# untitled.net
KiCad netlist of a schematic drawn in EAGLE
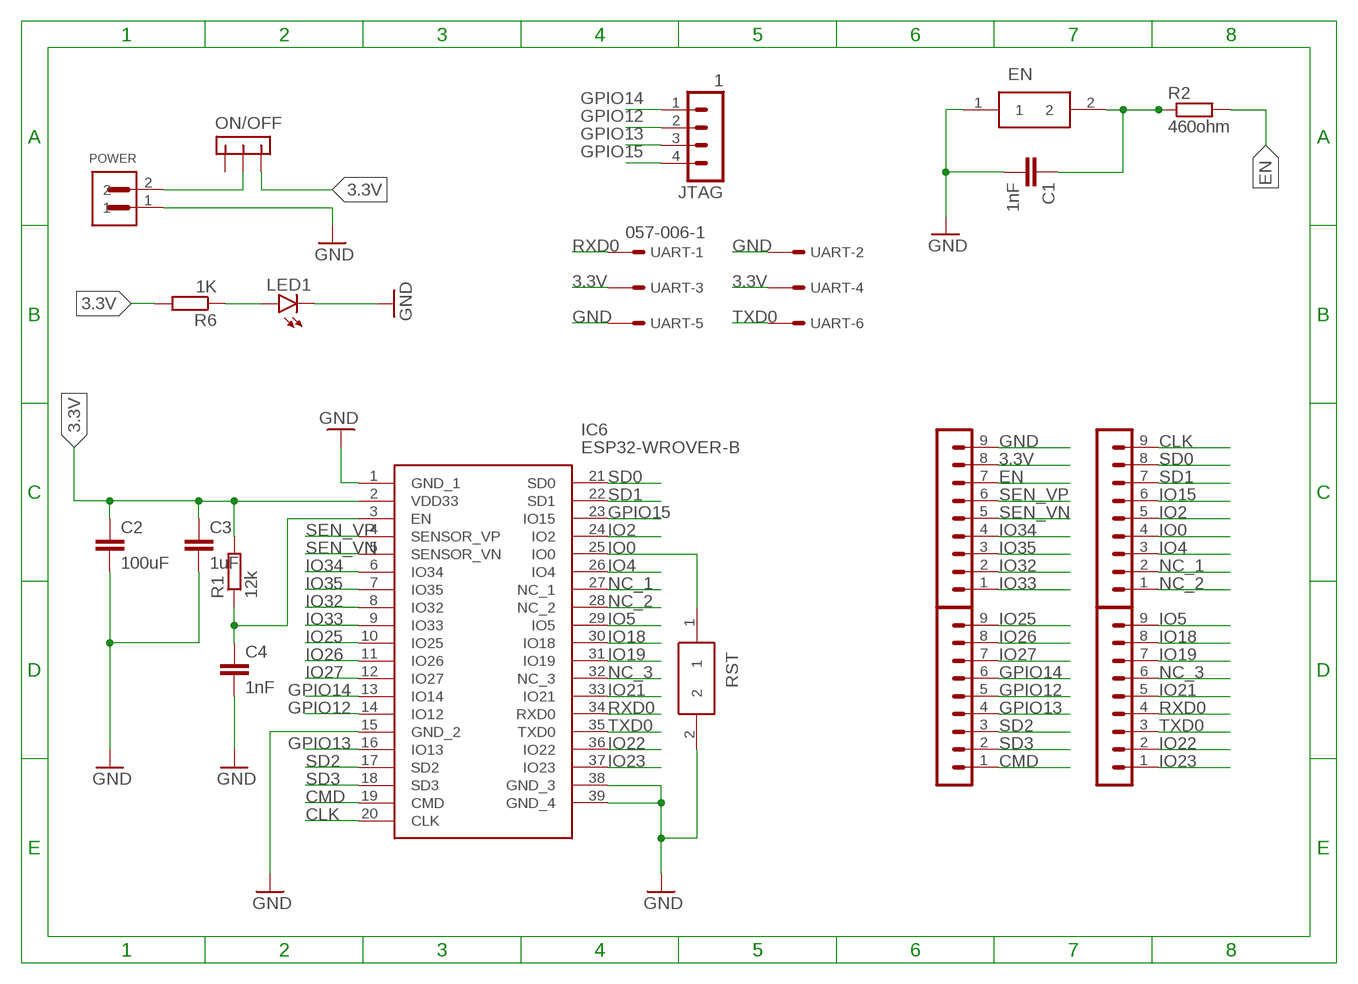
[diagram p0: schematic, sheet 1]

(export (version "E")
  (design (tool "Eeschema 10.0.6"))
  (components
    (comp (ref "C1")
      (value "1nF")
      (footprint "eagle-import:C0805")
      (libsource (lib "eagle-import") (part "C-EU_805C0805"))
    )
    (comp (ref "C2")
      (value "100uF")
      (footprint "eagle-import:C1206")
      (libsource (lib "eagle-import") (part "C-EU_1206C1206"))
    )
    (comp (ref "C3")
      (value "1uF")
      (footprint "eagle-import:C0805")
      (libsource (lib "eagle-import") (part "C-EU_805C0805"))
    )
    (comp (ref "C4")
      (value "1nF")
      (footprint "eagle-import:C0805")
      (libsource (lib "eagle-import") (part "C-EU_805C0805"))
    )
    (comp (ref "EN")
      (value "FSMSMTR")
      (footprint "eagle-import:FSMSM")
      (fields (field (name "MOUSER_PART_NUMBER") "506-FSMSMTR") (field (name "RS_PART_NUMBER") "1680547"))
      (libsource (lib "eagle-import") (part "FSMSMTR"))
    )
    (comp (ref "IC6")
      (value "ESP32-WROVER-B")
      (footprint "eagle-import:ESP32WROVERIB16MB")
      (fields (field (name "MOUSER_PART_NUMBER") "356-ESP32-WROVER-B"))
      (libsource (lib "eagle-import") (part "ESP32-WROVER-B"))
    )
    (comp (ref "JTAG")
      (value "1")
      (footprint "eagle-import:MA04-1")
      (libsource (lib "eagle-import") (part "MA04-1"))
    )
    (comp (ref "LED1")
      (value "LEDSMT1206")
      (footprint "eagle-import:1206")
      (libsource (lib "eagle-import") (part "LEDSMT1206"))
    )
    (comp (ref "ON/OFF")
      (value "-CON3")
      (footprint "eagle-import:CON3")
      (libsource (lib "eagle-import") (part "-CON3"))
    )
    (comp (ref "POWER")
      (value "S2B-PH-SM4-TB")
      (footprint "eagle-import:JST_S2B-PH-SM4-TB")
      (fields (field (name "MF") "JST Sales"))
      (libsource (lib "eagle-import") (part "S2B-PH-SM4-TB"))
    )
    (comp (ref "R1")
      (value "12k")
      (footprint "eagle-import:R0805")
      (libsource (lib "eagle-import") (part "R-EU_805R0805"))
    )
    (comp (ref "R2")
      (value "460ohm")
      (footprint "eagle-import:R0805")
      (libsource (lib "eagle-import") (part "R-EU_805R0805"))
    )
    (comp (ref "R6")
      (value "1K")
      (footprint "eagle-import:R1206")
      (libsource (lib "eagle-import") (part "R-EU_R1206"))
    )
    (comp (ref "RST")
      (value "FSMSMTR")
      (footprint "eagle-import:FSMSM")
      (fields (field (name "MOUSER_PART_NUMBER") "506-FSMSMTR") (field (name "RS_PART_NUMBER") "1680547"))
      (libsource (lib "eagle-import") (part "FSMSMTR"))
    )
    (comp (ref "SV1")
      (value "PINHEADER-1X9")
      (footprint "eagle-import:MA09-1")
      (libsource (lib "eagle-import") (part "PINHEADER-1X9"))
    )
    (comp (ref "SV2")
      (value "PINHEADER-1X9")
      (footprint "eagle-import:MA09-1")
      (libsource (lib "eagle-import") (part "PINHEADER-1X9"))
    )
    (comp (ref "SV5")
      (value "PINHEADER-1X9")
      (footprint "eagle-import:MA09-1")
      (libsource (lib "eagle-import") (part "PINHEADER-1X9"))
    )
    (comp (ref "SV6")
      (value "PINHEADER-1X9")
      (footprint "eagle-import:MA09-1")
      (libsource (lib "eagle-import") (part "PINHEADER-1X9"))
    )
    (comp (ref "UART")
      (value "057-006-1")
      (footprint "eagle-import:057-006-1")
      (libsource (lib "eagle-import") (part "057-006-1"))
    )
  )
  (nets
    (net (code "1") (name "3.3V") (class "Default")
      (node (ref "C2") (pin "1") (pinfunction "1_1") (pintype "passive"))
      (node (ref "C3") (pin "1") (pinfunction "1_1") (pintype "passive"))
      (node (ref "IC6") (pin "2") (pinfunction "VDD33_2") (pintype "bidirectional"))
      (node (ref "ON/OFF") (pin "P$1") (pinfunction "1_P$1") (pintype "passive"))
      (node (ref "R1") (pin "2") (pinfunction "2_2") (pintype "passive"))
      (node (ref "R6") (pin "2") (pinfunction "2_2") (pintype "passive"))
      (node (ref "SV5") (pin "8") (pinfunction "8_8") (pintype "passive"))
      (node (ref "UART") (pin "3") (pinfunction "S_3") (pintype "passive"))
      (node (ref "UART") (pin "4") (pinfunction "S_4") (pintype "passive"))
    )
    (net (code "2") (name "CLK") (class "Default")
      (node (ref "IC6") (pin "20") (pinfunction "CLK_20") (pintype "bidirectional"))
      (node (ref "SV1") (pin "9") (pinfunction "9_9") (pintype "passive"))
    )
    (net (code "3") (name "CMD") (class "Default")
      (node (ref "IC6") (pin "19") (pinfunction "CMD_19") (pintype "bidirectional"))
      (node (ref "SV6") (pin "1") (pinfunction "1_1") (pintype "passive"))
    )
    (net (code "4") (name "EN") (class "Default")
      (node (ref "C1") (pin "1") (pinfunction "1_1") (pintype "passive"))
      (node (ref "C4") (pin "1") (pinfunction "1_1") (pintype "passive"))
      (node (ref "EN") (pin "2") (pinfunction "2_2") (pintype "bidirectional"))
      (node (ref "IC6") (pin "3") (pinfunction "EN_3") (pintype "bidirectional"))
      (node (ref "R1") (pin "1") (pinfunction "1_1") (pintype "passive"))
      (node (ref "R2") (pin "1") (pinfunction "1_1") (pintype "passive"))
      (node (ref "R2") (pin "2") (pinfunction "2_2") (pintype "passive"))
      (node (ref "SV5") (pin "7") (pinfunction "7_7") (pintype "passive"))
    )
    (net (code "5") (name "GND") (class "Default")
      (node (ref "C1") (pin "2") (pinfunction "2_2") (pintype "passive"))
      (node (ref "C2") (pin "2") (pinfunction "2_2") (pintype "passive"))
      (node (ref "C3") (pin "2") (pinfunction "2_2") (pintype "passive"))
      (node (ref "C4") (pin "2") (pinfunction "2_2") (pintype "passive"))
      (node (ref "EN") (pin "1") (pinfunction "1_1") (pintype "bidirectional"))
      (node (ref "IC6") (pin "1") (pinfunction "GND_1_1") (pintype "bidirectional"))
      (node (ref "IC6") (pin "15") (pinfunction "GND_2_15") (pintype "bidirectional"))
      (node (ref "IC6") (pin "38") (pinfunction "GND_3_38") (pintype "bidirectional"))
      (node (ref "IC6") (pin "39") (pinfunction "GND_4_39") (pintype "bidirectional"))
      (node (ref "LED1") (pin "C") (pinfunction "C_C") (pintype "passive"))
      (node (ref "POWER") (pin "1") (pinfunction "1_1") (pintype "passive"))
      (node (ref "RST") (pin "2") (pinfunction "2_2") (pintype "bidirectional"))
      (node (ref "SV5") (pin "9") (pinfunction "9_9") (pintype "passive"))
      (node (ref "UART") (pin "2") (pinfunction "S_2") (pintype "passive"))
      (node (ref "UART") (pin "5") (pinfunction "S_5") (pintype "passive"))
    )
    (net (code "6") (name "GPIO12") (class "Default")
      (node (ref "IC6") (pin "14") (pinfunction "IO12_14") (pintype "bidirectional"))
      (node (ref "JTAG") (pin "2") (pinfunction "2_2") (pintype "passive"))
      (node (ref "SV6") (pin "5") (pinfunction "5_5") (pintype "passive"))
    )
    (net (code "7") (name "GPIO13") (class "Default")
      (node (ref "IC6") (pin "16") (pinfunction "IO13_16") (pintype "bidirectional"))
      (node (ref "JTAG") (pin "3") (pinfunction "3_3") (pintype "passive"))
      (node (ref "SV6") (pin "4") (pinfunction "4_4") (pintype "passive"))
    )
    (net (code "8") (name "GPIO14") (class "Default")
      (node (ref "IC6") (pin "13") (pinfunction "IO14_13") (pintype "bidirectional"))
      (node (ref "JTAG") (pin "1") (pinfunction "1_1") (pintype "passive"))
      (node (ref "SV6") (pin "6") (pinfunction "6_6") (pintype "passive"))
    )
    (net (code "9") (name "GPIO15") (class "Default")
      (node (ref "IC6") (pin "23") (pinfunction "IO15_23") (pintype "bidirectional"))
      (node (ref "JTAG") (pin "4") (pinfunction "4_4") (pintype "passive"))
    )
    (net (code "10") (name "IO0") (class "Default")
      (node (ref "IC6") (pin "25") (pinfunction "IO0_25") (pintype "bidirectional"))
      (node (ref "RST") (pin "1") (pinfunction "1_1") (pintype "bidirectional"))
      (node (ref "SV1") (pin "4") (pinfunction "4_4") (pintype "passive"))
    )
    (net (code "11") (name "IO2") (class "Default")
      (node (ref "IC6") (pin "24") (pinfunction "IO2_24") (pintype "bidirectional"))
      (node (ref "SV1") (pin "5") (pinfunction "5_5") (pintype "passive"))
    )
    (net (code "12") (name "IO4") (class "Default")
      (node (ref "IC6") (pin "26") (pinfunction "IO4_26") (pintype "bidirectional"))
      (node (ref "SV1") (pin "3") (pinfunction "3_3") (pintype "passive"))
    )
    (net (code "13") (name "IO5") (class "Default")
      (node (ref "IC6") (pin "29") (pinfunction "IO5_29") (pintype "bidirectional"))
      (node (ref "SV2") (pin "9") (pinfunction "9_9") (pintype "passive"))
    )
    (net (code "14") (name "IO15") (class "Default")
      (node (ref "SV1") (pin "6") (pinfunction "6_6") (pintype "passive"))
    )
    (net (code "15") (name "IO18") (class "Default")
      (node (ref "IC6") (pin "30") (pinfunction "IO18_30") (pintype "bidirectional"))
      (node (ref "SV2") (pin "8") (pinfunction "8_8") (pintype "passive"))
    )
    (net (code "16") (name "IO19") (class "Default")
      (node (ref "IC6") (pin "31") (pinfunction "IO19_31") (pintype "bidirectional"))
      (node (ref "SV2") (pin "7") (pinfunction "7_7") (pintype "passive"))
    )
    (net (code "17") (name "IO21") (class "Default")
      (node (ref "IC6") (pin "33") (pinfunction "IO21_33") (pintype "bidirectional"))
      (node (ref "SV2") (pin "5") (pinfunction "5_5") (pintype "passive"))
    )
    (net (code "18") (name "IO22") (class "Default")
      (node (ref "IC6") (pin "36") (pinfunction "IO22_36") (pintype "bidirectional"))
      (node (ref "SV2") (pin "2") (pinfunction "2_2") (pintype "passive"))
    )
    (net (code "19") (name "IO23") (class "Default")
      (node (ref "IC6") (pin "37") (pinfunction "IO23_37") (pintype "bidirectional"))
      (node (ref "SV2") (pin "1") (pinfunction "1_1") (pintype "passive"))
    )
    (net (code "20") (name "IO25") (class "Default")
      (node (ref "IC6") (pin "10") (pinfunction "IO25_10") (pintype "bidirectional"))
      (node (ref "SV6") (pin "9") (pinfunction "9_9") (pintype "passive"))
    )
    (net (code "21") (name "IO26") (class "Default")
      (node (ref "IC6") (pin "11") (pinfunction "IO26_11") (pintype "bidirectional"))
      (node (ref "SV6") (pin "8") (pinfunction "8_8") (pintype "passive"))
    )
    (net (code "22") (name "IO27") (class "Default")
      (node (ref "IC6") (pin "12") (pinfunction "IO27_12") (pintype "bidirectional"))
      (node (ref "SV6") (pin "7") (pinfunction "7_7") (pintype "passive"))
    )
    (net (code "23") (name "IO32") (class "Default")
      (node (ref "IC6") (pin "8") (pinfunction "IO32_8") (pintype "bidirectional"))
      (node (ref "SV5") (pin "2") (pinfunction "2_2") (pintype "passive"))
    )
    (net (code "24") (name "IO33") (class "Default")
      (node (ref "IC6") (pin "9") (pinfunction "IO33_9") (pintype "bidirectional"))
      (node (ref "SV5") (pin "1") (pinfunction "1_1") (pintype "passive"))
    )
    (net (code "25") (name "IO34") (class "Default")
      (node (ref "IC6") (pin "6") (pinfunction "IO34_6") (pintype "bidirectional"))
      (node (ref "SV5") (pin "4") (pinfunction "4_4") (pintype "passive"))
    )
    (net (code "26") (name "IO35") (class "Default")
      (node (ref "IC6") (pin "7") (pinfunction "IO35_7") (pintype "bidirectional"))
      (node (ref "SV5") (pin "3") (pinfunction "3_3") (pintype "passive"))
    )
    (net (code "27") (name "NC_1") (class "Default")
      (node (ref "IC6") (pin "27") (pinfunction "NC_1_27") (pintype "bidirectional"))
      (node (ref "SV1") (pin "2") (pinfunction "2_2") (pintype "passive"))
    )
    (net (code "28") (name "NC_2") (class "Default")
      (node (ref "IC6") (pin "28") (pinfunction "NC_2_28") (pintype "bidirectional"))
      (node (ref "SV1") (pin "1") (pinfunction "1_1") (pintype "passive"))
    )
    (net (code "29") (name "NC_3") (class "Default")
      (node (ref "IC6") (pin "32") (pinfunction "NC_3_32") (pintype "bidirectional"))
      (node (ref "SV2") (pin "6") (pinfunction "6_6") (pintype "passive"))
    )
    (net (code "30") (name "Net-(LED1-PadA)") (class "Default")
      (node (ref "LED1") (pin "A") (pinfunction "A_A") (pintype "passive"))
      (node (ref "R6") (pin "1") (pinfunction "1_1") (pintype "passive"))
    )
    (net (code "31") (name "Net-(ON/OFF-2)") (class "Default")
      (node (ref "ON/OFF") (pin "P$2") (pinfunction "2_P$2") (pintype "passive"))
      (node (ref "POWER") (pin "2") (pinfunction "2_2") (pintype "passive"))
    )
    (net (code "32") (name "RXD0") (class "Default")
      (node (ref "IC6") (pin "34") (pinfunction "RXD0_34") (pintype "bidirectional"))
      (node (ref "SV2") (pin "4") (pinfunction "4_4") (pintype "passive"))
      (node (ref "UART") (pin "1") (pinfunction "S_1") (pintype "passive"))
    )
    (net (code "33") (name "SD0") (class "Default")
      (node (ref "IC6") (pin "21") (pinfunction "SD0_21") (pintype "bidirectional"))
      (node (ref "SV1") (pin "8") (pinfunction "8_8") (pintype "passive"))
    )
    (net (code "34") (name "SD1") (class "Default")
      (node (ref "IC6") (pin "22") (pinfunction "SD1_22") (pintype "bidirectional"))
      (node (ref "SV1") (pin "7") (pinfunction "7_7") (pintype "passive"))
    )
    (net (code "35") (name "SD2") (class "Default")
      (node (ref "IC6") (pin "17") (pinfunction "SD2_17") (pintype "bidirectional"))
      (node (ref "SV6") (pin "3") (pinfunction "3_3") (pintype "passive"))
    )
    (net (code "36") (name "SD3") (class "Default")
      (node (ref "IC6") (pin "18") (pinfunction "SD3_18") (pintype "bidirectional"))
      (node (ref "SV6") (pin "2") (pinfunction "2_2") (pintype "passive"))
    )
    (net (code "37") (name "SEN_VN") (class "Default")
      (node (ref "IC6") (pin "5") (pinfunction "SENSOR_VN_5") (pintype "bidirectional"))
      (node (ref "SV5") (pin "5") (pinfunction "5_5") (pintype "passive"))
    )
    (net (code "38") (name "SEN_VP") (class "Default")
      (node (ref "IC6") (pin "4") (pinfunction "SENSOR_VP_4") (pintype "bidirectional"))
      (node (ref "SV5") (pin "6") (pinfunction "6_6") (pintype "passive"))
    )
    (net (code "39") (name "TXD0") (class "Default")
      (node (ref "IC6") (pin "35") (pinfunction "TXD0_35") (pintype "bidirectional"))
      (node (ref "SV2") (pin "3") (pinfunction "3_3") (pintype "passive"))
      (node (ref "UART") (pin "6") (pinfunction "S_6") (pintype "passive"))
    )
    (net (code "40") (name "unconnected-(ON/OFF-3-PadP$3)") (class "Default")
      (node (ref "ON/OFF") (pin "P$3") (pinfunction "3_P$3") (pintype "passive"))
    )
  )
)
